# BigBoard.net
KiCad netlist of a schematic drawn in EAGLE
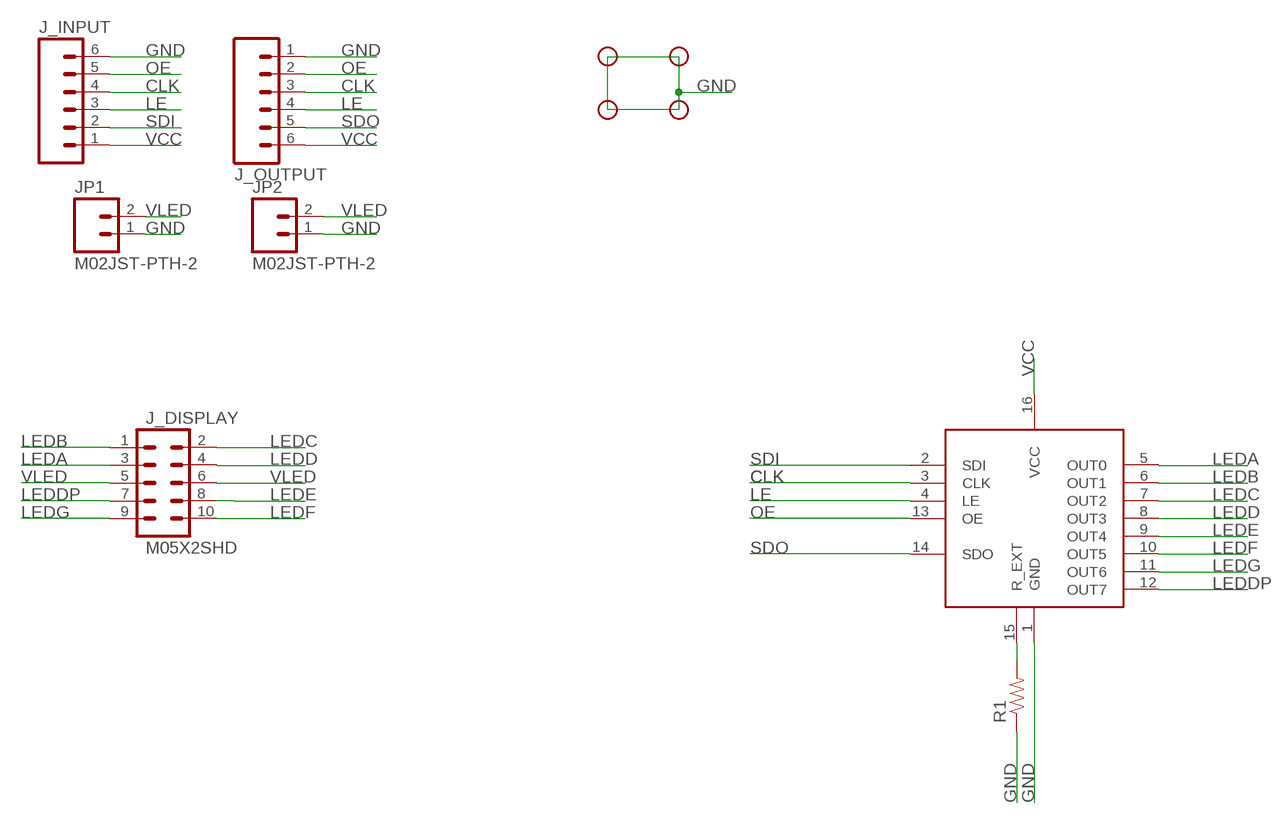
[diagram p0: schematic, sheet 1]

(export (version "E")
  (design (tool "Eeschema 10.0.6"))
  (components
    (comp (ref "JP1")
      (value "M02JST-PTH-2")
      (footprint "eagle-import:JST-2-PTH")
      (libsource (lib "eagle-import") (part "M02JST-PTH-2"))
    )
    (comp (ref "JP2")
      (value "M02JST-PTH-2")
      (footprint "eagle-import:JST-2-PTH")
      (libsource (lib "eagle-import") (part "M02JST-PTH-2"))
    )
    (comp (ref "J_DISPLAY")
      (value "M05X2SHD")
      (footprint "eagle-import:2X5-SHROUDED")
      (libsource (lib "eagle-import") (part "M05X2SHD"))
    )
    (comp (ref "J_INPUT")
      (value "M06POLAR")
      (footprint "eagle-import:MOLEX-1X6")
      (libsource (lib "eagle-import") (part "M06POLAR"))
    )
    (comp (ref "J_OUTPUT")
      (value "M06POLAR")
      (footprint "eagle-import:MOLEX-1X6")
      (libsource (lib "eagle-import") (part "M06POLAR"))
    )
    (comp (ref "R1")
      (value "RESISTOR0603-RES")
      (footprint "eagle-import:0603-RES")
      (libsource (lib "eagle-import") (part "RESISTOR0603-RES"))
    )
    (comp (ref "STANDOFF1")
      (value "STAND-OFF")
      (footprint "eagle-import:STAND-OFF")
      (libsource (lib "eagle-import") (part "STAND-OFF"))
    )
    (comp (ref "STANDOFF2")
      (value "STAND-OFF")
      (footprint "eagle-import:STAND-OFF")
      (libsource (lib "eagle-import") (part "STAND-OFF"))
    )
    (comp (ref "STANDOFF3")
      (value "STAND-OFF")
      (footprint "eagle-import:STAND-OFF")
      (libsource (lib "eagle-import") (part "STAND-OFF"))
    )
    (comp (ref "STANDOFF4")
      (value "STAND-OFF")
      (footprint "eagle-import:STAND-OFF")
      (libsource (lib "eagle-import") (part "STAND-OFF"))
    )
    (comp (ref "U$2")
      (value "A6278EA")
      (footprint "eagle-import:A6278EA")
      (libsource (lib "eagle-import") (part "A6278EA"))
    )
  )
  (nets
    (net (code "1") (name "/CLK") (class "Default")
      (node (ref "J_INPUT") (pin "4") (pinfunction "4_4") (pintype "passive"))
      (node (ref "J_OUTPUT") (pin "3") (pinfunction "3_3") (pintype "passive"))
      (node (ref "U$2") (pin "3") (pinfunction "CLK_3") (pintype "bidirectional"))
    )
    (net (code "2") (name "/GND") (class "Default")
      (node (ref "JP1") (pin "1") (pinfunction "1_1") (pintype "passive"))
      (node (ref "JP2") (pin "1") (pinfunction "1_1") (pintype "passive"))
      (node (ref "J_INPUT") (pin "6") (pinfunction "6_6") (pintype "passive"))
      (node (ref "J_OUTPUT") (pin "1") (pinfunction "1_1") (pintype "passive"))
      (node (ref "R1") (pin "1") (pinfunction "1_1") (pintype "passive"))
      (node (ref "U$2") (pin "1") (pinfunction "GND_1") (pintype "bidirectional"))
    )
    (net (code "3") (name "/LE") (class "Default")
      (node (ref "J_INPUT") (pin "3") (pinfunction "3_3") (pintype "passive"))
      (node (ref "J_OUTPUT") (pin "4") (pinfunction "4_4") (pintype "passive"))
      (node (ref "U$2") (pin "4") (pinfunction "LE_4") (pintype "bidirectional"))
    )
    (net (code "4") (name "/LEDA") (class "Default")
      (node (ref "J_DISPLAY") (pin "3") (pinfunction "3_3") (pintype "passive"))
      (node (ref "U$2") (pin "5") (pinfunction "OUT0_5") (pintype "bidirectional"))
    )
    (net (code "5") (name "/LEDB") (class "Default")
      (node (ref "J_DISPLAY") (pin "1") (pinfunction "1_1") (pintype "passive"))
      (node (ref "U$2") (pin "6") (pinfunction "OUT1_6") (pintype "bidirectional"))
    )
    (net (code "6") (name "/LEDC") (class "Default")
      (node (ref "J_DISPLAY") (pin "2") (pinfunction "2_2") (pintype "passive"))
      (node (ref "U$2") (pin "7") (pinfunction "OUT2_7") (pintype "bidirectional"))
    )
    (net (code "7") (name "/LEDD") (class "Default")
      (node (ref "J_DISPLAY") (pin "4") (pinfunction "4_4") (pintype "passive"))
      (node (ref "U$2") (pin "8") (pinfunction "OUT3_8") (pintype "bidirectional"))
    )
    (net (code "8") (name "/LEDDP") (class "Default")
      (node (ref "J_DISPLAY") (pin "7") (pinfunction "7_7") (pintype "passive"))
      (node (ref "U$2") (pin "12") (pinfunction "OUT7_12") (pintype "bidirectional"))
    )
    (net (code "9") (name "/LEDE") (class "Default")
      (node (ref "J_DISPLAY") (pin "8") (pinfunction "8_8") (pintype "passive"))
      (node (ref "U$2") (pin "9") (pinfunction "OUT4_9") (pintype "bidirectional"))
    )
    (net (code "10") (name "/LEDF") (class "Default")
      (node (ref "J_DISPLAY") (pin "10") (pinfunction "10_10") (pintype "passive"))
      (node (ref "U$2") (pin "10") (pinfunction "OUT5_10") (pintype "bidirectional"))
    )
    (net (code "11") (name "/LEDG") (class "Default")
      (node (ref "J_DISPLAY") (pin "9") (pinfunction "9_9") (pintype "passive"))
      (node (ref "U$2") (pin "11") (pinfunction "OUT6_11") (pintype "bidirectional"))
    )
    (net (code "12") (name "/OE") (class "Default")
      (node (ref "J_INPUT") (pin "5") (pinfunction "5_5") (pintype "passive"))
      (node (ref "J_OUTPUT") (pin "2") (pinfunction "2_2") (pintype "passive"))
      (node (ref "U$2") (pin "13") (pinfunction "OE_13") (pintype "bidirectional"))
    )
    (net (code "13") (name "/SDI") (class "Default")
      (node (ref "J_INPUT") (pin "2") (pinfunction "2_2") (pintype "passive"))
      (node (ref "U$2") (pin "2") (pinfunction "SDI_2") (pintype "bidirectional"))
    )
    (net (code "14") (name "/SDO") (class "Default")
      (node (ref "J_OUTPUT") (pin "5") (pinfunction "5_5") (pintype "passive"))
      (node (ref "U$2") (pin "14") (pinfunction "SDO_14") (pintype "bidirectional"))
    )
    (net (code "15") (name "/VCC") (class "Default")
      (node (ref "J_INPUT") (pin "1") (pinfunction "1_1") (pintype "passive"))
      (node (ref "J_OUTPUT") (pin "6") (pinfunction "6_6") (pintype "passive"))
      (node (ref "U$2") (pin "16") (pinfunction "VCC_16") (pintype "bidirectional"))
    )
    (net (code "16") (name "/VLED") (class "Default")
      (node (ref "JP1") (pin "2") (pinfunction "2_2") (pintype "passive"))
      (node (ref "JP2") (pin "2") (pinfunction "2_2") (pintype "passive"))
      (node (ref "J_DISPLAY") (pin "5") (pinfunction "5_5") (pintype "passive"))
      (node (ref "J_DISPLAY") (pin "6") (pinfunction "6_6") (pintype "passive"))
    )
    (net (code "17") (name "Net-(U$2-R_EXT)") (class "Default")
      (node (ref "R1") (pin "2") (pinfunction "2_2") (pintype "passive"))
      (node (ref "U$2") (pin "15") (pinfunction "R_EXT_15") (pintype "bidirectional"))
    )
  )
)
